# LEFT_AR0234.net
KiCad netlist of a schematic drawn in Altium Designer
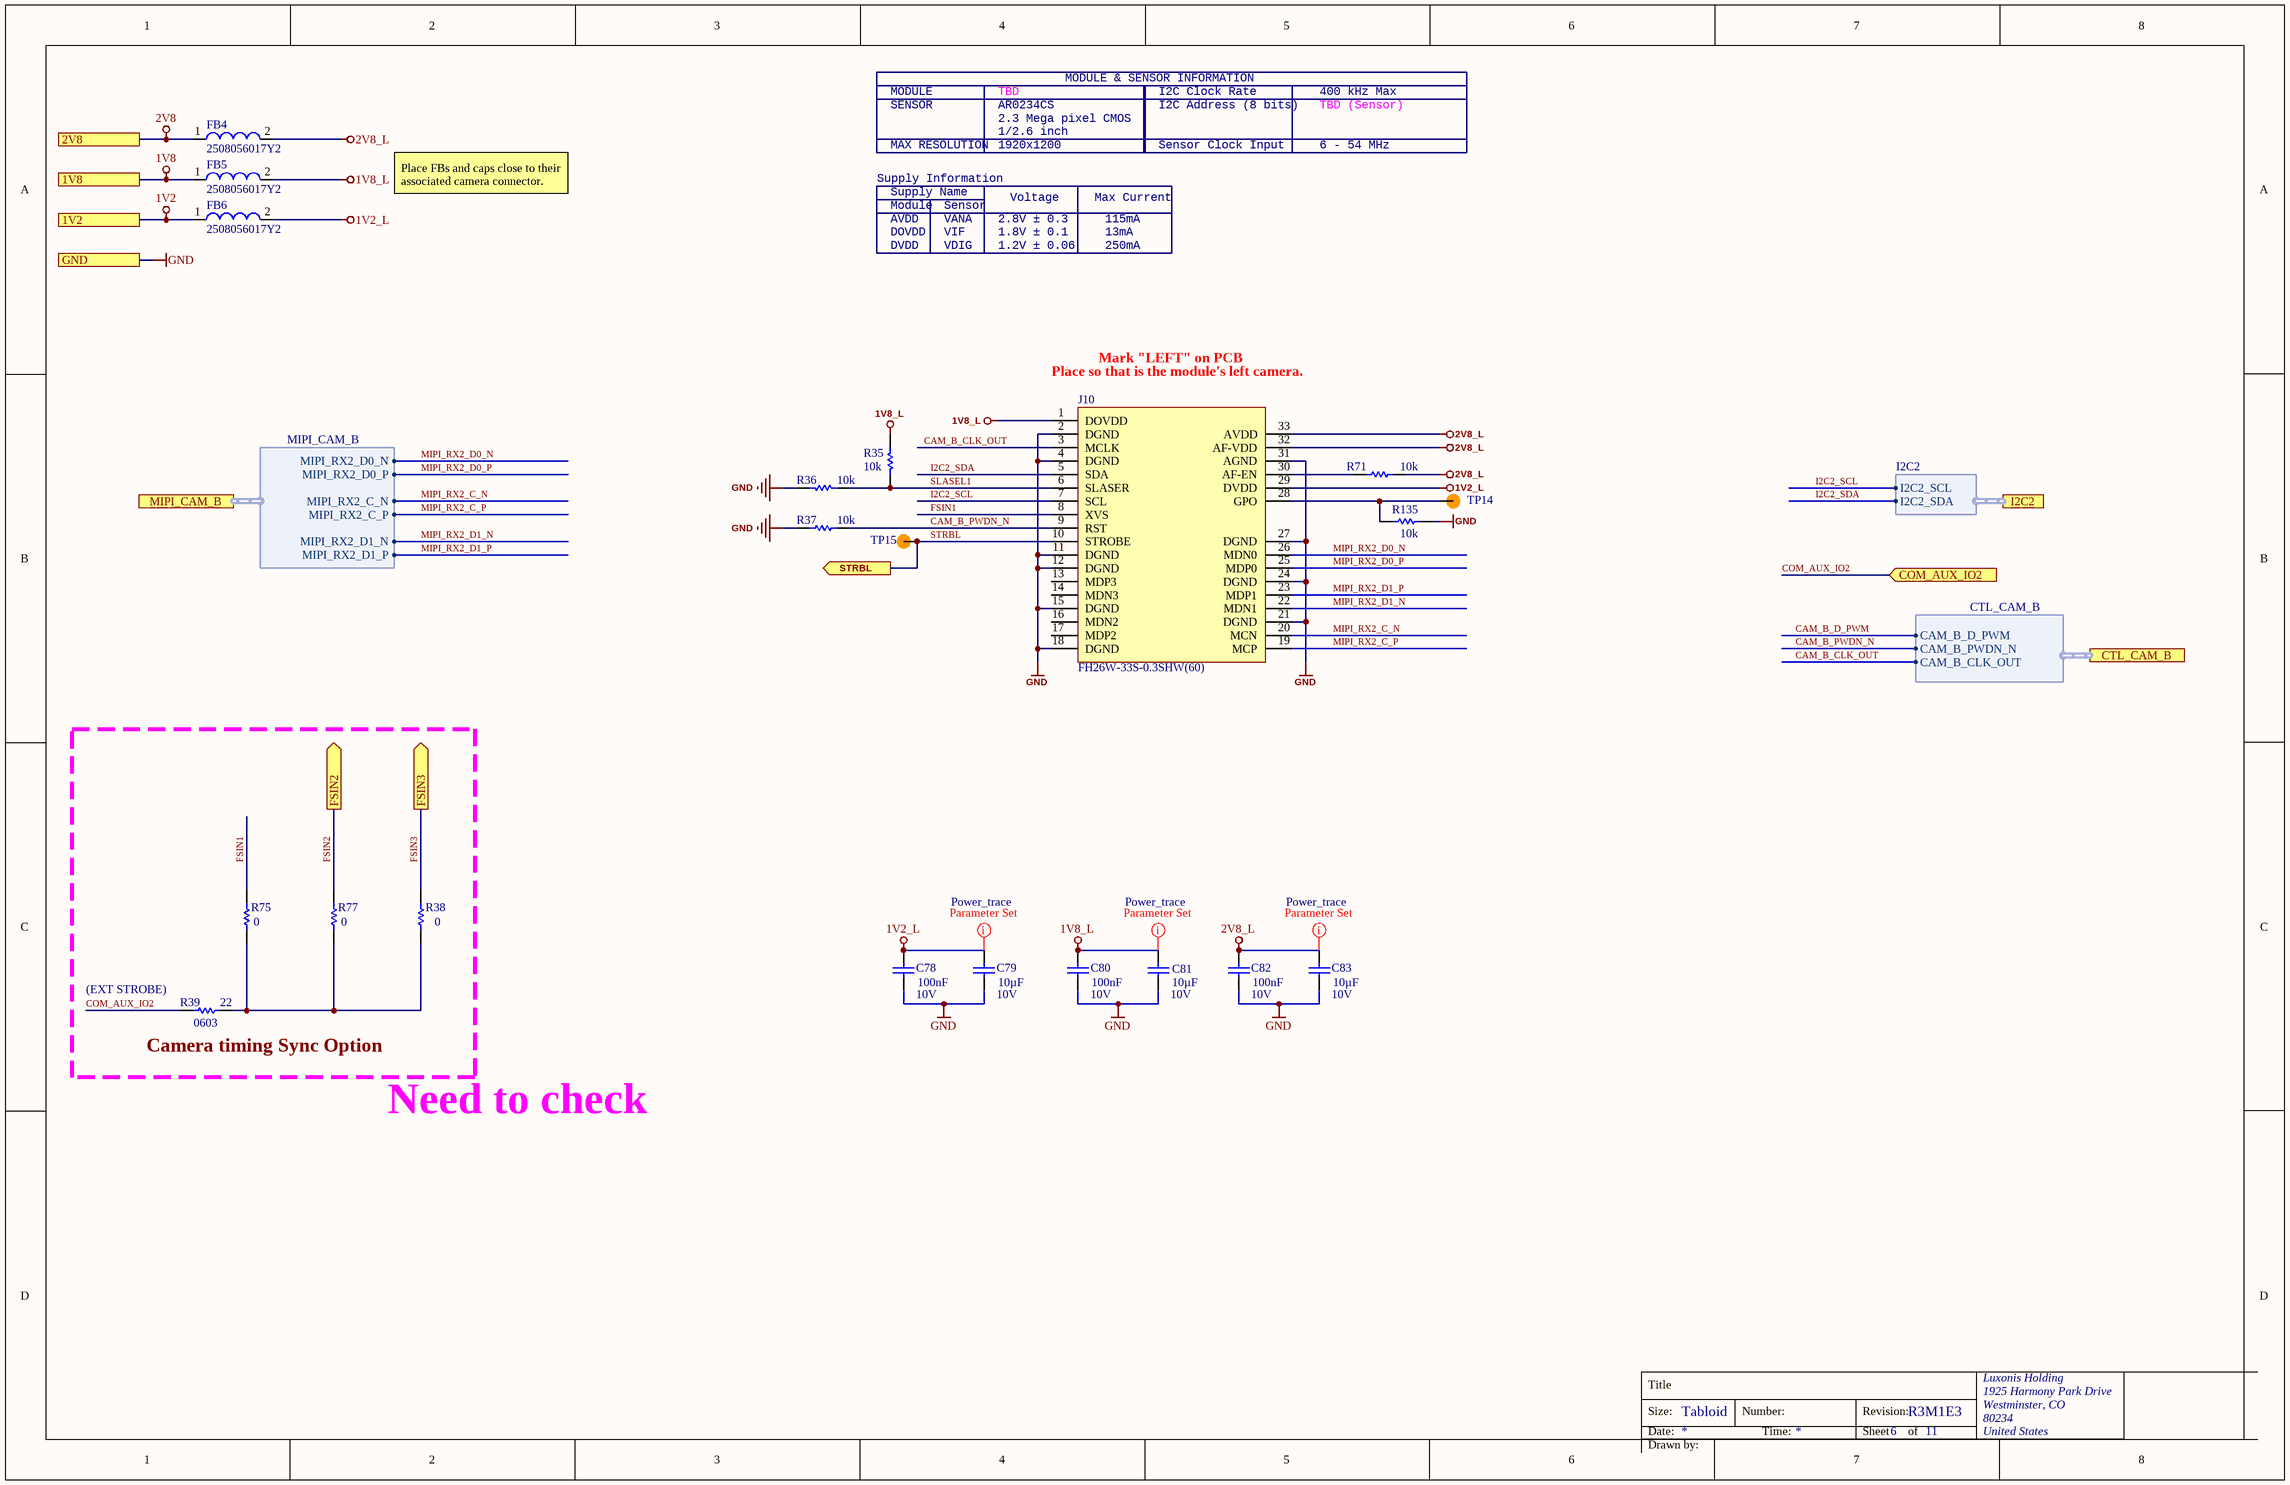
[diagram p0: LEFT_AR0234.SchDoc]

(export (version "E")
  (design (tool "Eeschema 10.0.6"))
  (components
    (comp (ref "C78")
      (value "100nF")
      (footprint "CAPC0402(1005)70_L")
      (description "CAP CER 0.1UF 10V X7R 0402 5%")
      (fields
        (field (name "TOLERANCE") "5%")
        (field (name "VOLTAGE RATING") "10V")
        (field (name "Comment") "GRM155R71A104JA01D")
      )
      (libsource (lib "Luxonis LLC") (part "GRM188R61C475KAAJD"))
    )
    (comp (ref "C79")
      (value "10µF")
      (footprint "CAPC0603(1608)100_L")
      (description "CAP CER 10UF 10V X5R 0603 20%")
      (fields
        (field (name "TOLERANCE") "20%")
        (field (name "VOLTAGE RATING") "10V")
        (field (name "Comment") "GRM188R61A106ME69D")
      )
      (libsource (lib "Luxonis LLC") (part "LLL153C70G474ME17E"))
    )
    (comp (ref "C80")
      (value "100nF")
      (footprint "CAPC0402(1005)70_L")
      (description "CAP CER 0.1UF 10V X7R 0402 5%")
      (fields
        (field (name "TOLERANCE") "5%")
        (field (name "VOLTAGE RATING") "10V")
        (field (name "Comment") "GRM155R71A104JA01D")
      )
      (libsource (lib "Luxonis LLC") (part "GRM188R61C475KAAJD"))
    )
    (comp (ref "C81")
      (value "10µF")
      (footprint "CAPC0603(1608)100_L")
      (description "CAP CER 10UF 10V X5R 0603 20%")
      (fields
        (field (name "TOLERANCE") "20%")
        (field (name "VOLTAGE RATING") "10V")
        (field (name "Comment") "GRM188R61A106ME69D")
      )
      (libsource (lib "Luxonis LLC") (part "LLL153C70G474ME17E"))
    )
    (comp (ref "C82")
      (value "100nF")
      (footprint "CAPC0402(1005)70_L")
      (description "CAP CER 0.1UF 10V X7R 0402 5%")
      (fields
        (field (name "TOLERANCE") "5%")
        (field (name "VOLTAGE RATING") "10V")
        (field (name "Comment") "GRM155R71A104JA01D")
      )
      (libsource (lib "Luxonis LLC") (part "GRM188R61C475KAAJD"))
    )
    (comp (ref "C83")
      (value "10µF")
      (footprint "CAPC0603(1608)100_L")
      (description "CAP CER 10UF 10V X5R 0603 20%")
      (fields
        (field (name "TOLERANCE") "20%")
        (field (name "VOLTAGE RATING") "10V")
        (field (name "Comment") "GRM188R61A106ME69D")
      )
      (libsource (lib "Luxonis LLC") (part "LLL153C70G474ME17E"))
    )
    (comp (ref "FB4")
      (value "2508056017Y2")
      (footprint "2508056017Y2")
      (description "FERRITE BEAD, 0.1OHM, 2A, 0805, 600R/100MHz")
      (fields (field (name "TOLERANCE") "25%"))
      (libsource (lib "Luxonis LLC") (part "2508056017Y2"))
    )
    (comp (ref "FB5")
      (value "2508056017Y2")
      (footprint "2508056017Y2")
      (description "FERRITE BEAD, 0.1OHM, 2A, 0805, 600R/100MHz")
      (fields (field (name "TOLERANCE") "25%"))
      (libsource (lib "Luxonis LLC") (part "2508056017Y2"))
    )
    (comp (ref "FB6")
      (value "2508056017Y2")
      (footprint "2508056017Y2")
      (description "FERRITE BEAD, 0.1OHM, 2A, 0805, 600R/100MHz")
      (fields (field (name "TOLERANCE") "25%"))
      (libsource (lib "Luxonis LLC") (part "2508056017Y2"))
    )
    (comp (ref "J10")
      (value "FH26W-33S-0.3SHW(60)")
      (footprint "FH26W-33S-0.3SHW(60)")
      (description "FFC/FPC Connector, 33 Contact(s), 1 Row(s), Female, Right Angle, Surface Mount Terminal")
      (libsource (lib "Luxonis LLC") (part "FH26W-33S-0.3SHW(60)"))
    )
    (comp (ref "R35")
      (value "10k")
      (footprint "RESC0402(1005)_L")
      (description "RES SMD 10K OHM 1% 1/16W 0402")
      (fields (field (name "TOLERANCE") "1%") (field (name "Comment") "RC0402FR-1310KL"))
      (libsource (lib "Luxonis LLC") (part "RC0402FR-0722RL_1"))
    )
    (comp (ref "R36")
      (value "10k")
      (footprint "RESC0402(1005)_L")
      (description "RES SMD 10K OHM 1% 1/16W 0402")
      (fields (field (name "TOLERANCE") "1%") (field (name "Comment") "RC0402FR-1310KL"))
      (libsource (lib "Luxonis LLC") (part "RC0402FR-0722RL_1"))
    )
    (comp (ref "R37")
      (value "10k")
      (footprint "RESC0402(1005)_L")
      (description "RES SMD 10K OHM 1% 1/16W 0402")
      (fields (field (name "TOLERANCE") "1%") (field (name "Comment") "RC0402FR-1310KL"))
      (libsource (lib "Luxonis LLC") (part "RC0402FR-0722RL_1"))
    )
    (comp (ref "R38")
      (value "0")
      (footprint "RESC0603(1608)_L")
      (description "RES SMD 0 OHM 5% 1/10W 0603")
      (fields (field (name "TOLERANCE") "5%") (field (name "Comment") "CRCW06030000Z0EA"))
      (libsource (lib "Luxonis LLC") (part "RC0402FR-0722RL_1"))
    )
    (comp (ref "R39")
      (value "22")
      (footprint "RESC0603(1608)_L")
      (description "RES SMD 22 OHM 1% 1/10W 0603")
      (fields
        (field (name "CASE/PACKAGE") "0603")
        (field (name "TOLERANCE") "1%")
        (field (name "Comment") "RC0603FR-0722RL")
      )
      (libsource (lib "Luxonis LLC") (part "Default resistor symbol"))
    )
    (comp (ref "R71")
      (value "10k")
      (footprint "RESC0402(1005)_L")
      (description "RES SMD 10K OHM 1% 1/16W 0402")
      (fields (field (name "TOLERANCE") "1%") (field (name "Comment") "RC0402FR-1310KL"))
      (libsource (lib "Luxonis LLC") (part "RC0402FR-0722RL_1"))
    )
    (comp (ref "R75")
      (value "0")
      (footprint "RESC0603(1608)_L")
      (description "RES SMD 0 OHM 5% 1/10W 0603")
      (fields (field (name "TOLERANCE") "5%") (field (name "Comment") "CRCW06030000Z0EA"))
      (libsource (lib "Luxonis LLC") (part "RC0402FR-0722RL_1"))
    )
    (comp (ref "R77")
      (value "0")
      (footprint "RESC0603(1608)_L")
      (description "RES SMD 0 OHM 5% 1/10W 0603")
      (fields (field (name "TOLERANCE") "5%") (field (name "Comment") "CRCW06030000Z0EA"))
      (libsource (lib "Luxonis LLC") (part "RC0402FR-0722RL_1"))
    )
    (comp (ref "R135")
      (value "10k")
      (footprint "RESC0402(1005)_L")
      (description "RES SMD 10K OHM 1% 1/16W 0402")
      (fields (field (name "TOLERANCE") "1%") (field (name "Comment") "RC0402FR-1310KL"))
      (libsource (lib "Luxonis LLC") (part "RC0402FR-0722RL_1"))
    )
    (comp (ref "TP14")
      (value "TEST_POINT")
      (footprint "TP100_200_NS")
      (libsource (lib "Luxonis LLC") (part "TEST_POINT"))
    )
    (comp (ref "TP15")
      (value "TEST_POINT")
      (footprint "TP100_200_NS")
      (libsource (lib "Luxonis LLC") (part "TEST_POINT"))
    )
  )
  (nets
    (net (code "4") (name "/CAM_B_CLK_OUT") (class "Default")
      (node (ref "J10") (pin "3") (pinfunction "MCLK_3") (pintype "passive"))
    )
    (net (code "6") (name "/CAM_B_PWDN_N") (class "Default")
      (node (ref "J10") (pin "9") (pinfunction "RST_9") (pintype "passive"))
      (node (ref "R37") (pin "1") (pinfunction "1_1") (pintype "passive"))
    )
    (net (code "7") (name "/COM_AUX_IO2") (class "Default")
      (node (ref "R39") (pin "2") (pinfunction "2_2") (pintype "passive"))
    )
    (net (code "8") (name "/FSIN1") (class "Default")
      (node (ref "J10") (pin "8") (pinfunction "XVS_8") (pintype "passive"))
      (node (ref "R75") (pin "2") (pinfunction "2_2") (pintype "passive"))
    )
    (net (code "9") (name "/FSIN2") (class "Default")
      (node (ref "R77") (pin "2") (pinfunction "2_2") (pintype "passive"))
    )
    (net (code "10") (name "/FSIN3") (class "Default")
      (node (ref "R38") (pin "2") (pinfunction "2_2") (pintype "passive"))
    )
    (net (code "11") (name "/I2C2_SCL") (class "Default")
      (node (ref "J10") (pin "7") (pinfunction "SCL_7") (pintype "passive"))
    )
    (net (code "12") (name "/I2C2_SDA") (class "Default")
      (node (ref "J10") (pin "5") (pinfunction "SDA_5") (pintype "passive"))
    )
    (net (code "13") (name "/MIPI_RX2_C_N") (class "Default")
      (node (ref "J10") (pin "20") (pinfunction "MCN_20") (pintype "passive"))
    )
    (net (code "14") (name "/MIPI_RX2_C_P") (class "Default")
      (node (ref "J10") (pin "19") (pinfunction "MCP_19") (pintype "passive"))
    )
    (net (code "15") (name "/MIPI_RX2_D0_N") (class "Default")
      (node (ref "J10") (pin "26") (pinfunction "MDN0_26") (pintype "passive"))
    )
    (net (code "16") (name "/MIPI_RX2_D0_P") (class "Default")
      (node (ref "J10") (pin "25") (pinfunction "MDP0_25") (pintype "passive"))
    )
    (net (code "17") (name "/MIPI_RX2_D1_N") (class "Default")
      (node (ref "J10") (pin "22") (pinfunction "MDN1_22") (pintype "passive"))
    )
    (net (code "18") (name "/MIPI_RX2_D1_P") (class "Default")
      (node (ref "J10") (pin "23") (pinfunction "MDP1_23") (pintype "passive"))
    )
    (net (code "19") (name "/SLASEL1") (class "Default")
      (node (ref "J10") (pin "6") (pinfunction "SLASER_6") (pintype "passive"))
      (node (ref "R35") (pin "2") (pinfunction "2_2") (pintype "passive"))
      (node (ref "R36") (pin "2") (pinfunction "2_2") (pintype "passive"))
    )
    (net (code "20") (name "/STRBL") (class "Default")
      (node (ref "J10") (pin "10") (pinfunction "STROBE_10") (pintype "passive"))
      (node (ref "TP15") (pin "1") (pintype "passive"))
    )
    (net (code "24") (name "1V2") (class "Default")
      (node (ref "FB6") (pin "1") (pinfunction "1_1") (pintype "passive"))
    )
    (net (code "25") (name "1V2_L") (class "Default")
      (node (ref "C78") (pin "2") (pinfunction "2_2") (pintype "passive"))
      (node (ref "C79") (pin "2") (pinfunction "2_2") (pintype "passive"))
      (node (ref "FB6") (pin "2") (pinfunction "2_2") (pintype "passive"))
      (node (ref "J10") (pin "29") (pinfunction "DVDD_29") (pintype "passive"))
    )
    (net (code "26") (name "1V8") (class "Default")
      (node (ref "FB5") (pin "1") (pinfunction "1_1") (pintype "passive"))
    )
    (net (code "27") (name "1V8_L") (class "Default")
      (node (ref "C80") (pin "2") (pinfunction "2_2") (pintype "passive"))
      (node (ref "C81") (pin "2") (pinfunction "2_2") (pintype "passive"))
      (node (ref "FB5") (pin "2") (pinfunction "2_2") (pintype "passive"))
      (node (ref "J10") (pin "1") (pinfunction "DOVDD_1") (pintype "passive"))
      (node (ref "R35") (pin "1") (pinfunction "1_1") (pintype "passive"))
    )
    (net (code "28") (name "2V8") (class "Default")
      (node (ref "FB4") (pin "1") (pinfunction "1_1") (pintype "passive"))
    )
    (net (code "29") (name "2V8_L") (class "Default")
      (node (ref "C82") (pin "2") (pinfunction "2_2") (pintype "passive"))
      (node (ref "C83") (pin "2") (pinfunction "2_2") (pintype "passive"))
      (node (ref "FB4") (pin "2") (pinfunction "2_2") (pintype "passive"))
      (node (ref "J10") (pin "32") (pinfunction "AF-VDD_32") (pintype "passive"))
      (node (ref "J10") (pin "33") (pinfunction "AVDD_33") (pintype "passive"))
      (node (ref "R71") (pin "2") (pinfunction "2_2") (pintype "passive"))
    )
    (net (code "30") (name "GND") (class "Default")
      (node (ref "C78") (pin "1") (pinfunction "1_1") (pintype "passive"))
      (node (ref "C79") (pin "1") (pinfunction "1_1") (pintype "passive"))
      (node (ref "C80") (pin "1") (pinfunction "1_1") (pintype "passive"))
      (node (ref "C81") (pin "1") (pinfunction "1_1") (pintype "passive"))
      (node (ref "C82") (pin "1") (pinfunction "1_1") (pintype "passive"))
      (node (ref "C83") (pin "1") (pinfunction "1_1") (pintype "passive"))
      (node (ref "J10") (pin "11") (pinfunction "DGND_11") (pintype "passive"))
      (node (ref "J10") (pin "12") (pinfunction "DGND_12") (pintype "passive"))
      (node (ref "J10") (pin "15") (pinfunction "DGND_15") (pintype "passive"))
      (node (ref "J10") (pin "18") (pinfunction "DGND_18") (pintype "passive"))
      (node (ref "J10") (pin "2") (pinfunction "DGND_2") (pintype "passive"))
      (node (ref "J10") (pin "21") (pinfunction "DGND_21") (pintype "passive"))
      (node (ref "J10") (pin "24") (pinfunction "DGND_24") (pintype "passive"))
      (node (ref "J10") (pin "27") (pinfunction "DGND_27") (pintype "passive"))
      (node (ref "J10") (pin "31") (pinfunction "AGND_31") (pintype "passive"))
      (node (ref "J10") (pin "4") (pinfunction "DGND_4") (pintype "passive"))
      (node (ref "R135") (pin "2") (pinfunction "2_2") (pintype "passive"))
      (node (ref "R36") (pin "1") (pinfunction "1_1") (pintype "passive"))
      (node (ref "R37") (pin "2") (pinfunction "2_2") (pintype "passive"))
    )
    (net (code "31") (name "Net-(J10-AF-EN)") (class "Default")
      (node (ref "J10") (pin "30") (pinfunction "AF-EN_30") (pintype "passive"))
      (node (ref "R71") (pin "1") (pinfunction "1_1") (pintype "passive"))
    )
    (net (code "32") (name "Net-(J10-GPO)") (class "Default")
      (node (ref "J10") (pin "28") (pinfunction "GPO_28") (pintype "passive"))
      (node (ref "R135") (pin "1") (pinfunction "1_1") (pintype "passive"))
      (node (ref "TP14") (pin "1") (pintype "passive"))
    )
    (net (code "33") (name "Net-(R38-Pad1)") (class "Default")
      (node (ref "R38") (pin "1") (pinfunction "1_1") (pintype "passive"))
      (node (ref "R39") (pin "1") (pinfunction "1_1") (pintype "passive"))
      (node (ref "R75") (pin "1") (pinfunction "1_1") (pintype "passive"))
      (node (ref "R77") (pin "1") (pinfunction "1_1") (pintype "passive"))
    )
    (net (code "34") (name "unconnected-(J10-MDN2-Pad16)") (class "Default")
      (node (ref "J10") (pin "16") (pinfunction "MDN2_16") (pintype "passive"))
    )
    (net (code "35") (name "unconnected-(J10-MDN3-Pad14)") (class "Default")
      (node (ref "J10") (pin "14") (pinfunction "MDN3_14") (pintype "passive"))
    )
    (net (code "36") (name "unconnected-(J10-MDP2-Pad17)") (class "Default")
      (node (ref "J10") (pin "17") (pinfunction "MDP2_17") (pintype "passive"))
    )
    (net (code "37") (name "unconnected-(J10-MDP3-Pad13)") (class "Default")
      (node (ref "J10") (pin "13") (pinfunction "MDP3_13") (pintype "passive"))
    )
  )
)
